# mapleCUx_large_085.net
KiCad netlist of a schematic drawn in EAGLE
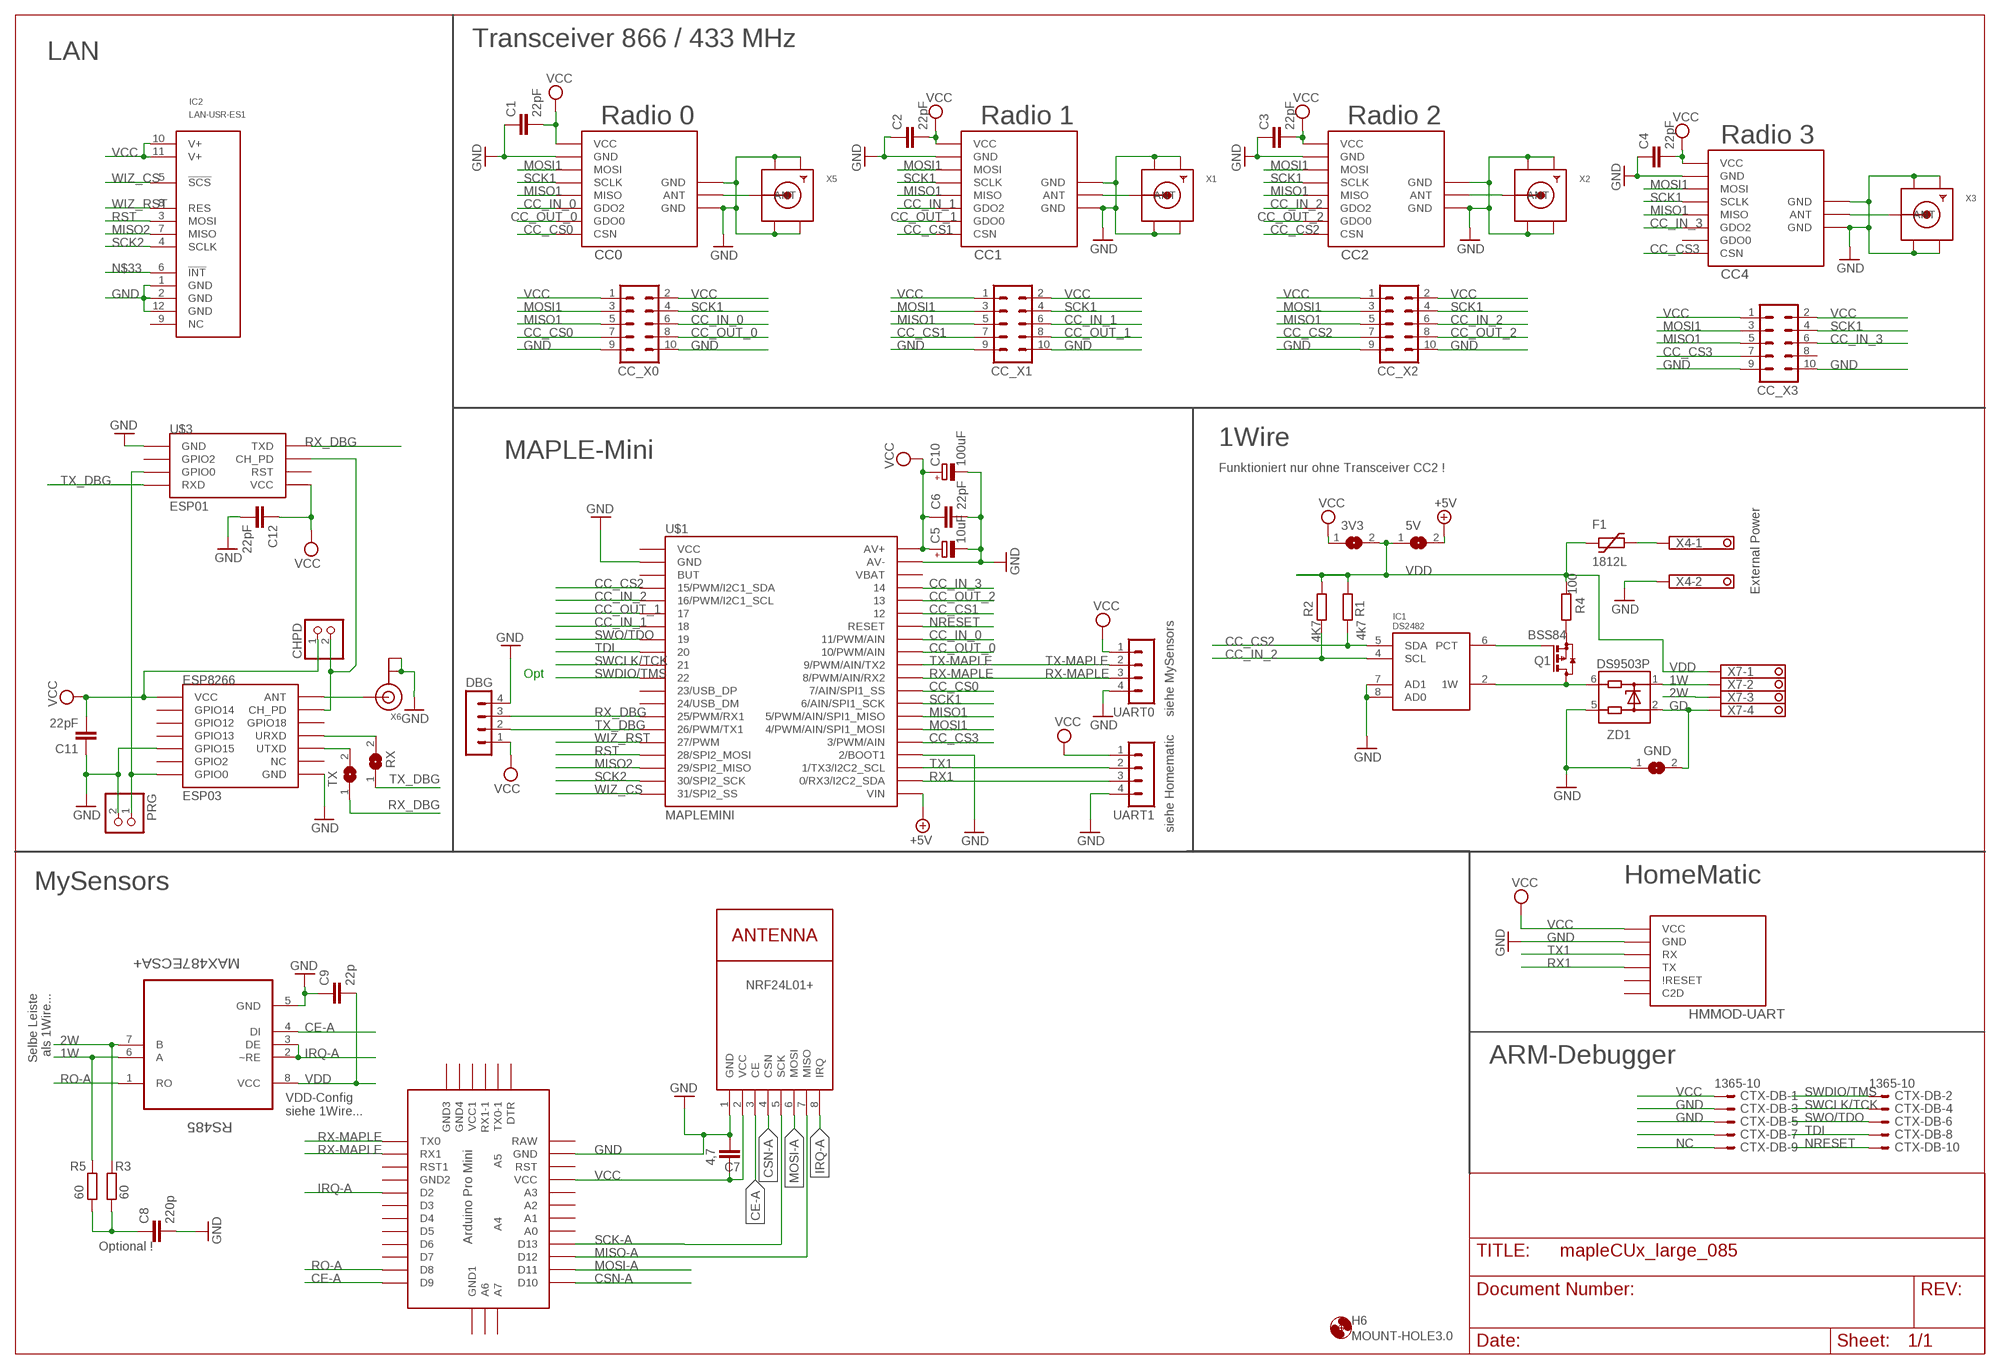
[diagram p0: schematic, sheet 1]

(export (version "E")
  (design (tool "Eeschema 10.0.6"))
  (components
    (comp (ref "3V3") (value "SJ") (footprint "eagle-import:SJ") (libsource (lib "eagle-import") (part "SJ")))
    (comp (ref "5V") (value "SJ") (footprint "eagle-import:SJ") (libsource (lib "eagle-import") (part "SJ")))
    (comp (ref "C1")
      (value "22pF")
      (footprint "eagle-import:C0805")
      (libsource (lib "eagle-import") (part "C-EUC0805"))
    )
    (comp (ref "C2")
      (value "22pF")
      (footprint "eagle-import:C0805")
      (libsource (lib "eagle-import") (part "C-EUC0805"))
    )
    (comp (ref "C3")
      (value "22pF")
      (footprint "eagle-import:C0805")
      (libsource (lib "eagle-import") (part "C-EUC0805"))
    )
    (comp (ref "C4")
      (value "22pF")
      (footprint "eagle-import:C0805")
      (libsource (lib "eagle-import") (part "C-EUC0805"))
    )
    (comp (ref "C5")
      (value "10uF")
      (footprint "eagle-import:R_2012-12W")
      (libsource (lib "eagle-import") (part "CPOL-EUR/2012-12W"))
    )
    (comp (ref "C6")
      (value "22pF")
      (footprint "eagle-import:C0805")
      (libsource (lib "eagle-import") (part "C-EUC0805"))
    )
    (comp (ref "C7")
      (value "4,7")
      (footprint "eagle-import:C1210")
      (libsource (lib "eagle-import") (part "C-EUC1210"))
    )
    (comp (ref "C8")
      (value "220p")
      (footprint "eagle-import:C0805")
      (libsource (lib "eagle-import") (part "C-EUC0805"))
    )
    (comp (ref "C9")
      (value "22p")
      (footprint "eagle-import:C0805")
      (libsource (lib "eagle-import") (part "C-EUC0805"))
    )
    (comp (ref "C10")
      (value "100uF")
      (footprint "eagle-import:E5-8,5")
      (libsource (lib "eagle-import") (part "CPOL-EUE5-8.5"))
    )
    (comp (ref "C11")
      (value "22pF")
      (footprint "eagle-import:C0805")
      (libsource (lib "eagle-import") (part "C-EUC0805"))
    )
    (comp (ref "C12")
      (value "22pF")
      (footprint "eagle-import:C0805")
      (libsource (lib "eagle-import") (part "C-EUC0805"))
    )
    (comp (ref "CC0")
      (value "CC1101")
      (footprint "eagle-import:CC1101_MODULE1_SMD")
      (libsource (lib "eagle-import") (part "CC1101_MODULE1SMD"))
    )
    (comp (ref "CC1")
      (value "CC1101_MODULE1SMD")
      (footprint "eagle-import:CC1101_MODULE1_SMD")
      (libsource (lib "eagle-import") (part "CC1101_MODULE1SMD"))
    )
    (comp (ref "CC2")
      (value "CC1101_MODULE1SMD")
      (footprint "eagle-import:CC1101_MODULE1_SMD")
      (libsource (lib "eagle-import") (part "CC1101_MODULE1SMD"))
    )
    (comp (ref "CC4")
      (value "CC1101_MODULE1SMD")
      (footprint "eagle-import:CC1101_MODULE1_SMD")
      (libsource (lib "eagle-import") (part "CC1101_MODULE1SMD"))
    )
    (comp (ref "CC_X0")
      (value "MA05-2")
      (footprint "eagle-import:MA05-2")
      (libsource (lib "eagle-import") (part "MA05-2"))
    )
    (comp (ref "CC_X1")
      (value "MA05-2")
      (footprint "eagle-import:MA05-2")
      (libsource (lib "eagle-import") (part "MA05-2"))
    )
    (comp (ref "CC_X2")
      (value "MA05-2")
      (footprint "eagle-import:MA05-2")
      (libsource (lib "eagle-import") (part "MA05-2"))
    )
    (comp (ref "CC_X3")
      (value "MA05-2")
      (footprint "eagle-import:MA05-2")
      (libsource (lib "eagle-import") (part "MA05-2"))
    )
    (comp (ref "CHPD")
      (value "PINHD-1X2")
      (footprint "eagle-import:1X02")
      (libsource (lib "eagle-import") (part "PINHD-1X2"))
    )
    (comp (ref "CTX-DB")
      (value "1365-10")
      (footprint "eagle-import:1365-10")
      (libsource (lib "eagle-import") (part "1365-10"))
    )
    (comp (ref "DBG")
      (value "MA04-1")
      (footprint "eagle-import:MA04-1")
      (libsource (lib "eagle-import") (part "MA04-1"))
    )
    (comp (ref "ESP8266")
      (value "ESP03")
      (footprint "eagle-import:ESP03")
      (libsource (lib "eagle-import") (part "ESP03"))
    )
    (comp (ref "F1")
      (value "1812L")
      (footprint "eagle-import:1812L")
      (libsource (lib "eagle-import") (part "1812L"))
    )
    (comp (ref "GND") (value "SJ") (footprint "eagle-import:SJ") (libsource (lib "eagle-import") (part "SJ")))
    (comp (ref "H6")
      (value "MOUNT-HOLE3.0")
      (footprint "eagle-import:3,0")
      (libsource (lib "eagle-import") (part "MOUNT-HOLE3.0"))
    )
    (comp (ref "HMMOD-UART")
      (value "HM-MOD-UARTDIL")
      (footprint "eagle-import:HM-MOD-UART-DIL")
      (libsource (lib "eagle-import") (part "HM-MOD-UARTDIL"))
    )
    (comp (ref "IC1")
      (value "DS2482")
      (footprint "eagle-import:SO08")
      (libsource (lib "eagle-import") (part "DS2482-100S"))
    )
    (comp (ref "IC2")
      (value "LAN-USR-ES1")
      (footprint "eagle-import:USR-ES1")
      (libsource (lib "eagle-import") (part "LAN-USR-ES1"))
    )
    (comp (ref "NRF24L01+")
      (value "NRF24L01+")
      (footprint "eagle-import:WIRELESS-NRF24L01")
      (libsource (lib "eagle-import") (part "WIRELESS-NRF24L01"))
    )
    (comp (ref "PRG")
      (value "PINHD-1X2")
      (footprint "eagle-import:1X02")
      (libsource (lib "eagle-import") (part "PINHD-1X2"))
    )
    (comp (ref "Q1")
      (value "BSS84")
      (footprint "eagle-import:SOT23")
      (libsource (lib "eagle-import") (part "BSS84"))
    )
    (comp (ref "R1")
      (value "4k7")
      (footprint "eagle-import:R0805")
      (libsource (lib "eagle-import") (part "R-EU_R0805"))
    )
    (comp (ref "R2")
      (value "4K7")
      (footprint "eagle-import:R0805")
      (libsource (lib "eagle-import") (part "R-EU_R0805"))
    )
    (comp (ref "R3")
      (value "60")
      (footprint "eagle-import:R0805")
      (libsource (lib "eagle-import") (part "R-EU_R0805"))
    )
    (comp (ref "R4")
      (value "100")
      (footprint "eagle-import:R0805")
      (libsource (lib "eagle-import") (part "R-EU_R0805"))
    )
    (comp (ref "R5")
      (value "60")
      (footprint "eagle-import:R0805")
      (libsource (lib "eagle-import") (part "R-EU_R0805"))
    )
    (comp (ref "RS485")
      (value "MAX487ECSA+")
      (footprint "eagle-import:SOIC127P600X175-8N")
      (libsource (lib "eagle-import") (part "MAX487ECSA+"))
    )
    (comp (ref "RX") (value "SJ") (footprint "eagle-import:SJ") (libsource (lib "eagle-import") (part "SJ")))
    (comp (ref "TX") (value "SJ") (footprint "eagle-import:SJ") (libsource (lib "eagle-import") (part "SJ")))
    (comp (ref "U$1")
      (value "MAPLEMINI")
      (footprint "eagle-import:20-DIP")
      (libsource (lib "eagle-import") (part "MAPLEMINI"))
    )
    (comp (ref "U$2")
      (value "ABK-PRO-MINI")
      (footprint "eagle-import:ABK-PRO-MINI")
      (libsource (lib "eagle-import") (part "ABK-PRO-MINI"))
    )
    (comp (ref "U$3")
      (value "ESP01")
      (footprint "eagle-import:ESP01")
      (libsource (lib "eagle-import") (part "ESP01"))
    )
    (comp (ref "UART0")
      (value "MA04-1")
      (footprint "eagle-import:MA04-1")
      (libsource (lib "eagle-import") (part "MA04-1"))
    )
    (comp (ref "UART1")
      (value "MA04-1")
      (footprint "eagle-import:MA04-1")
      (libsource (lib "eagle-import") (part "MA04-1"))
    )
    (comp (ref "X1")
      (value "SMACONNECTOR_EDGE_UFL")
      (footprint "eagle-import:SMA_EDGELAUNCH_UFL")
      (libsource (lib "eagle-import") (part "SMACONNECTOR_EDGE_UFL"))
    )
    (comp (ref "X2")
      (value "SMACONNECTOR_EDGE_UFL")
      (footprint "eagle-import:SMA_EDGELAUNCH_UFL")
      (libsource (lib "eagle-import") (part "SMACONNECTOR_EDGE_UFL"))
    )
    (comp (ref "X3")
      (value "SMACONNECTOR_EDGE_UFL")
      (footprint "eagle-import:SMA_EDGELAUNCH_UFL")
      (libsource (lib "eagle-import") (part "SMACONNECTOR_EDGE_UFL"))
    )
    (comp (ref "X4")
      (value "1751248")
      (footprint "eagle-import:1751248")
      (libsource (lib "eagle-import") (part "1751248"))
    )
    (comp (ref "X5")
      (value "SMACONNECTOR_EDGE_UFL")
      (footprint "eagle-import:SMA_EDGELAUNCH_UFL")
      (libsource (lib "eagle-import") (part "SMACONNECTOR_EDGE_UFL"))
    )
    (comp (ref "X6")
      (value "ANTENNA_U.FL")
      (footprint "eagle-import:U.FL")
      (libsource (lib "eagle-import") (part "ANTENNA_U.FL"))
    )
    (comp (ref "X7")
      (value "1751264")
      (footprint "eagle-import:1751264")
      (libsource (lib "eagle-import") (part "1751264"))
    )
    (comp (ref "ZD1")
      (value "DS9503P")
      (footprint "eagle-import:TSOC6")
      (libsource (lib "eagle-import") (part "DS9503P"))
    )
  )
  (nets
    (net (code "1") (name "+5V") (class "Default")
      (node (ref "5V") (pin "2") (pinfunction "2_2") (pintype "passive"))
      (node (ref "U$1") (pin "21") (pinfunction "VIN_21") (pintype "bidirectional"))
    )
    (net (code "2") (name "/1W") (class "Default")
      (node (ref "R5") (pin "2") (pinfunction "2_2") (pintype "passive"))
      (node (ref "RS485") (pin "6") (pinfunction "A_6") (pintype "bidirectional"))
      (node (ref "X7") (pin "2") (pinfunction "K_2") (pintype "passive"))
      (node (ref "ZD1") (pin "1") (pinfunction "P$1_1") (pintype "passive"))
    )
    (net (code "3") (name "/2W") (class "Default")
      (node (ref "R3") (pin "2") (pinfunction "2_2") (pintype "passive"))
      (node (ref "RS485") (pin "7") (pinfunction "B_7") (pintype "bidirectional"))
      (node (ref "X7") (pin "3") (pinfunction "K_3") (pintype "passive"))
    )
    (net (code "4") (name "/CC_CS0") (class "Default")
      (node (ref "CC0") (pin "CSN") (pinfunction "CSN_CSN") (pintype "bidirectional"))
      (node (ref "CC_X0") (pin "7") (pinfunction "7_7") (pintype "passive"))
      (node (ref "U$1") (pin "29") (pinfunction "7/AIN/SPI1_SS_29") (pintype "bidirectional"))
    )
    (net (code "5") (name "/CC_CS1") (class "Default")
      (node (ref "CC1") (pin "CSN") (pinfunction "CSN_CSN") (pintype "bidirectional"))
      (node (ref "CC_X1") (pin "7") (pinfunction "7_7") (pintype "passive"))
      (node (ref "U$1") (pin "35") (pinfunction "12_35") (pintype "bidirectional"))
    )
    (net (code "6") (name "/CC_CS2") (class "Default")
      (node (ref "CC2") (pin "CSN") (pinfunction "CSN_CSN") (pintype "bidirectional"))
      (node (ref "CC_X2") (pin "7") (pinfunction "7_7") (pintype "passive"))
      (node (ref "IC1") (pin "5") (pinfunction "SDA_5") (pintype "bidirectional"))
      (node (ref "R1") (pin "2") (pinfunction "2_2") (pintype "passive"))
      (node (ref "U$1") (pin "4") (pinfunction "15/PWM/I2C1_SDA_4") (pintype "bidirectional"))
    )
    (net (code "7") (name "/CC_CS3") (class "Default")
      (node (ref "CC4") (pin "CSN") (pinfunction "CSN_CSN") (pintype "bidirectional"))
      (node (ref "CC_X3") (pin "7") (pinfunction "7_7") (pintype "passive"))
      (node (ref "U$1") (pin "25") (pinfunction "3/PWM/AIN_25") (pintype "bidirectional"))
    )
    (net (code "8") (name "/CC_IN_0") (class "Default")
      (node (ref "CC0") (pin "GDO2") (pinfunction "GDO2_GDO2") (pintype "bidirectional"))
      (node (ref "CC_X0") (pin "6") (pinfunction "6_6") (pintype "passive"))
      (node (ref "U$1") (pin "33") (pinfunction "11/PWM/AIN_33") (pintype "bidirectional"))
    )
    (net (code "9") (name "/CC_IN_1") (class "Default")
      (node (ref "CC1") (pin "GDO2") (pinfunction "GDO2_GDO2") (pintype "bidirectional"))
      (node (ref "CC_X1") (pin "6") (pinfunction "6_6") (pintype "passive"))
      (node (ref "U$1") (pin "7") (pinfunction "18_7") (pintype "bidirectional"))
    )
    (net (code "10") (name "/CC_IN_2") (class "Default")
      (node (ref "CC2") (pin "GDO2") (pinfunction "GDO2_GDO2") (pintype "bidirectional"))
      (node (ref "CC_X2") (pin "6") (pinfunction "6_6") (pintype "passive"))
      (node (ref "IC1") (pin "4") (pinfunction "SCL_4") (pintype "input"))
      (node (ref "R2") (pin "2") (pinfunction "2_2") (pintype "passive"))
      (node (ref "U$1") (pin "5") (pinfunction "16/PWM/I2C1_SCL_5") (pintype "bidirectional"))
    )
    (net (code "11") (name "/CC_IN_3") (class "Default")
      (node (ref "CC4") (pin "GDO2") (pinfunction "GDO2_GDO2") (pintype "bidirectional"))
      (node (ref "CC_X3") (pin "6") (pinfunction "6_6") (pintype "passive"))
      (node (ref "U$1") (pin "37") (pinfunction "14_37") (pintype "bidirectional"))
    )
    (net (code "12") (name "/CC_OUT_0") (class "Default")
      (node (ref "CC0") (pin "GDO0") (pinfunction "GDO0_GDO0") (pintype "bidirectional"))
      (node (ref "CC_X0") (pin "8") (pinfunction "8_8") (pintype "passive"))
      (node (ref "U$1") (pin "32") (pinfunction "10/PWM/AIN_32") (pintype "bidirectional"))
    )
    (net (code "13") (name "/CC_OUT_1") (class "Default")
      (node (ref "CC1") (pin "GDO0") (pinfunction "GDO0_GDO0") (pintype "bidirectional"))
      (node (ref "CC_X1") (pin "8") (pinfunction "8_8") (pintype "passive"))
      (node (ref "U$1") (pin "6") (pinfunction "17_6") (pintype "bidirectional"))
    )
    (net (code "14") (name "/CC_OUT_2") (class "Default")
      (node (ref "CC2") (pin "GDO0") (pinfunction "GDO0_GDO0") (pintype "bidirectional"))
      (node (ref "CC_X2") (pin "8") (pinfunction "8_8") (pintype "passive"))
      (node (ref "U$1") (pin "36") (pinfunction "13_36") (pintype "bidirectional"))
    )
    (net (code "15") (name "/GD") (class "Default")
      (node (ref "GND") (pin "2") (pinfunction "2_2") (pintype "passive"))
      (node (ref "X7") (pin "4") (pinfunction "K_4") (pintype "passive"))
      (node (ref "ZD1") (pin "2") (pinfunction "P$2_2") (pintype "passive"))
    )
    (net (code "16") (name "/MISO-A") (class "Default")
      (node (ref "NRF24L01+") (pin "7") (pinfunction "MISO_7") (pintype "bidirectional"))
      (node (ref "U$2") (pin "D12") (pinfunction "D12_D12") (pintype "bidirectional"))
    )
    (net (code "17") (name "/MISO1") (class "Default")
      (node (ref "CC0") (pin "MISO") (pinfunction "MISO_MISO") (pintype "bidirectional"))
      (node (ref "CC1") (pin "MISO") (pinfunction "MISO_MISO") (pintype "bidirectional"))
      (node (ref "CC2") (pin "MISO") (pinfunction "MISO_MISO") (pintype "bidirectional"))
      (node (ref "CC4") (pin "MISO") (pinfunction "MISO_MISO") (pintype "bidirectional"))
      (node (ref "CC_X0") (pin "5") (pinfunction "5_5") (pintype "passive"))
      (node (ref "CC_X1") (pin "5") (pinfunction "5_5") (pintype "passive"))
      (node (ref "CC_X2") (pin "5") (pinfunction "5_5") (pintype "passive"))
      (node (ref "CC_X3") (pin "5") (pinfunction "5_5") (pintype "passive"))
      (node (ref "U$1") (pin "27") (pinfunction "5/PWM/AIN/SPI1_MISO_27") (pintype "bidirectional"))
    )
    (net (code "18") (name "/MISO2") (class "Default")
      (node (ref "IC2") (pin "7") (pinfunction "MISO_7") (pintype "bidirectional"))
      (node (ref "U$1") (pin "18") (pinfunction "29/SPI2_MISO_18") (pintype "bidirectional"))
    )
    (net (code "19") (name "/MOSI1") (class "Default")
      (node (ref "CC0") (pin "MOSI") (pinfunction "MOSI_MOSI") (pintype "bidirectional"))
      (node (ref "CC1") (pin "MOSI") (pinfunction "MOSI_MOSI") (pintype "bidirectional"))
      (node (ref "CC2") (pin "MOSI") (pinfunction "MOSI_MOSI") (pintype "bidirectional"))
      (node (ref "CC4") (pin "MOSI") (pinfunction "MOSI_MOSI") (pintype "bidirectional"))
      (node (ref "CC_X0") (pin "3") (pinfunction "3_3") (pintype "passive"))
      (node (ref "CC_X1") (pin "3") (pinfunction "3_3") (pintype "passive"))
      (node (ref "CC_X2") (pin "3") (pinfunction "3_3") (pintype "passive"))
      (node (ref "CC_X3") (pin "3") (pinfunction "3_3") (pintype "passive"))
      (node (ref "U$1") (pin "26") (pinfunction "4/PWM/AIN/SPI1_MOSI_26") (pintype "bidirectional"))
    )
    (net (code "20") (name "/N$33") (class "Default")
      (node (ref "IC2") (pin "6") (pinfunction "~{INT}_6") (pintype "output"))
    )
    (net (code "21") (name "/NC") (class "Default")
      (node (ref "CTX-DB") (pin "9") (pinfunction "S_9") (pintype "passive"))
    )
    (net (code "22") (name "/NRESET") (class "Default")
      (node (ref "CTX-DB") (pin "10") (pinfunction "S_10") (pintype "passive"))
      (node (ref "U$1") (pin "34") (pinfunction "RESET_34") (pintype "bidirectional"))
    )
    (net (code "23") (name "/RO-A") (class "Default")
      (node (ref "RS485") (pin "1") (pinfunction "RO_1") (pintype "output"))
      (node (ref "U$2") (pin "D8") (pinfunction "D8_D8") (pintype "bidirectional"))
    )
    (net (code "24") (name "/RST") (class "Default")
      (node (ref "IC2") (pin "3") (pinfunction "MOSI_3") (pintype "bidirectional"))
      (node (ref "U$1") (pin "17") (pinfunction "28/SPI2_MOSI_17") (pintype "bidirectional"))
    )
    (net (code "25") (name "/RX-MAPLE") (class "Default")
      (node (ref "U$1") (pin "30") (pinfunction "8/PWM/AIN/RX2_30") (pintype "bidirectional"))
      (node (ref "U$2") (pin "RX1") (pinfunction "RX1_RX1") (pintype "bidirectional"))
      (node (ref "U$2") (pin "TX0") (pinfunction "TX0_TX0") (pintype "bidirectional"))
      (node (ref "UART0") (pin "3") (pinfunction "3_3") (pintype "passive"))
    )
    (net (code "26") (name "/RX1") (class "Default")
      (node (ref "HMMOD-UART") (pin "5") (pinfunction "TX_5") (pintype "bidirectional"))
      (node (ref "U$1") (pin "22") (pinfunction "0/RX3/I2C2_SDA_22") (pintype "bidirectional"))
      (node (ref "UART1") (pin "3") (pinfunction "3_3") (pintype "passive"))
    )
    (net (code "27") (name "/RX_DBG") (class "Default")
      (node (ref "DBG") (pin "3") (pinfunction "3_3") (pintype "passive"))
      (node (ref "TX") (pin "1") (pinfunction "1_1") (pintype "passive"))
      (node (ref "U$1") (pin "14") (pinfunction "25/PWM/RX1_14") (pintype "bidirectional"))
      (node (ref "U$3") (pin "TX") (pinfunction "TXD_TX") (pintype "bidirectional"))
    )
    (net (code "28") (name "/SCK-A") (class "Default")
      (node (ref "NRF24L01+") (pin "5") (pinfunction "SCK_5") (pintype "bidirectional"))
      (node (ref "U$2") (pin "D13") (pinfunction "D13_D13") (pintype "bidirectional"))
    )
    (net (code "29") (name "/SCK1") (class "Default")
      (node (ref "CC0") (pin "SCLK") (pinfunction "SCLK_SCLK") (pintype "bidirectional"))
      (node (ref "CC1") (pin "SCLK") (pinfunction "SCLK_SCLK") (pintype "bidirectional"))
      (node (ref "CC2") (pin "SCLK") (pinfunction "SCLK_SCLK") (pintype "bidirectional"))
      (node (ref "CC4") (pin "SCLK") (pinfunction "SCLK_SCLK") (pintype "bidirectional"))
      (node (ref "CC_X0") (pin "4") (pinfunction "4_4") (pintype "passive"))
      (node (ref "CC_X1") (pin "4") (pinfunction "4_4") (pintype "passive"))
      (node (ref "CC_X2") (pin "4") (pinfunction "4_4") (pintype "passive"))
      (node (ref "CC_X3") (pin "4") (pinfunction "4_4") (pintype "passive"))
      (node (ref "U$1") (pin "28") (pinfunction "6/AIN/SPI1_SCK_28") (pintype "bidirectional"))
    )
    (net (code "30") (name "/SCK2") (class "Default")
      (node (ref "IC2") (pin "4") (pinfunction "SCLK_4") (pintype "input"))
      (node (ref "U$1") (pin "19") (pinfunction "30/SPI2_SCK_19") (pintype "bidirectional"))
    )
    (net (code "31") (name "/SWCLK{slash}TCK") (class "Default")
      (node (ref "CTX-DB") (pin "4") (pinfunction "S_4") (pintype "passive"))
      (node (ref "U$1") (pin "10") (pinfunction "21_10") (pintype "bidirectional"))
    )
    (net (code "32") (name "/SWDIO{slash}TMS") (class "Default")
      (node (ref "CTX-DB") (pin "2") (pinfunction "S_2") (pintype "passive"))
      (node (ref "U$1") (pin "11") (pinfunction "22_11") (pintype "bidirectional"))
    )
    (net (code "33") (name "/SWO{slash}TDO") (class "Default")
      (node (ref "CTX-DB") (pin "6") (pinfunction "S_6") (pintype "passive"))
      (node (ref "U$1") (pin "8") (pinfunction "19_8") (pintype "bidirectional"))
    )
    (net (code "34") (name "/TDI") (class "Default")
      (node (ref "CTX-DB") (pin "8") (pinfunction "S_8") (pintype "passive"))
      (node (ref "U$1") (pin "9") (pinfunction "20_9") (pintype "bidirectional"))
    )
    (net (code "35") (name "/TX-MAPLE") (class "Default")
      (node (ref "U$1") (pin "31") (pinfunction "9/PWM/AIN/TX2_31") (pintype "bidirectional"))
      (node (ref "UART0") (pin "2") (pinfunction "2_2") (pintype "passive"))
    )
    (net (code "36") (name "/TX1") (class "Default")
      (node (ref "HMMOD-UART") (pin "6") (pinfunction "RX_6") (pintype "bidirectional"))
      (node (ref "U$1") (pin "23") (pinfunction "1/TX3/I2C2_SCL_23") (pintype "bidirectional"))
      (node (ref "UART1") (pin "2") (pinfunction "2_2") (pintype "passive"))
    )
    (net (code "37") (name "/TX_DBG") (class "Default")
      (node (ref "DBG") (pin "2") (pinfunction "2_2") (pintype "passive"))
      (node (ref "RX") (pin "1") (pinfunction "1_1") (pintype "passive"))
      (node (ref "U$1") (pin "15") (pinfunction "26/PWM/TX1_15") (pintype "bidirectional"))
      (node (ref "U$3") (pin "RX") (pinfunction "RXD_RX") (pintype "bidirectional"))
    )
    (net (code "38") (name "/VDD") (class "Default")
      (node (ref "3V3") (pin "2") (pinfunction "2_2") (pintype "passive"))
      (node (ref "5V") (pin "1") (pinfunction "1_1") (pintype "passive"))
      (node (ref "C9") (pin "2") (pinfunction "2_2") (pintype "passive"))
      (node (ref "F1") (pin "P$1") (pinfunction "1_P$1") (pintype "passive"))
      (node (ref "R1") (pin "1") (pinfunction "1_1") (pintype "passive"))
      (node (ref "R2") (pin "1") (pinfunction "1_1") (pintype "passive"))
      (node (ref "R4") (pin "2") (pinfunction "2_2") (pintype "passive"))
      (node (ref "RS485") (pin "8") (pinfunction "VCC_8") (pintype "power_in"))
      (node (ref "X7") (pin "1") (pinfunction "K_1") (pintype "passive"))
    )
    (net (code "39") (name "/WIZ_CS") (class "Default")
      (node (ref "IC2") (pin "5") (pinfunction "~{SCS}_5") (pintype "input"))
      (node (ref "U$1") (pin "20") (pinfunction "31/SPI2_SS_20") (pintype "bidirectional"))
    )
    (net (code "40") (name "/WIZ_RST") (class "Default")
      (node (ref "IC2") (pin "8") (pinfunction "RES_8") (pintype "input"))
      (node (ref "U$1") (pin "16") (pinfunction "27/PWM_16") (pintype "bidirectional"))
    )
    (net (code "41") (name "CE-A") (class "Default")
      (node (ref "NRF24L01+") (pin "3") (pinfunction "CE_3") (pintype "bidirectional"))
      (node (ref "RS485") (pin "4") (pinfunction "DI_4") (pintype "input"))
      (node (ref "U$2") (pin "D9") (pinfunction "D9_D9") (pintype "bidirectional"))
    )
    (net (code "42") (name "CSN-A") (class "Default")
      (node (ref "NRF24L01+") (pin "4") (pinfunction "CSN_4") (pintype "bidirectional"))
      (node (ref "U$2") (pin "D10") (pinfunction "D10_D10") (pintype "bidirectional"))
    )
    (net (code "43") (name "GND") (class "Default")
      (node (ref "C1") (pin "1") (pinfunction "1_1") (pintype "passive"))
      (node (ref "C10") (pin "-") (pinfunction "-_-") (pintype "passive"))
      (node (ref "C11") (pin "1") (pinfunction "1_1") (pintype "passive"))
      (node (ref "C12") (pin "2") (pinfunction "2_2") (pintype "passive"))
      (node (ref "C2") (pin "1") (pinfunction "1_1") (pintype "passive"))
      (node (ref "C3") (pin "1") (pinfunction "1_1") (pintype "passive"))
      (node (ref "C4") (pin "1") (pinfunction "1_1") (pintype "passive"))
      (node (ref "C5") (pin "-") (pinfunction "-_-") (pintype "passive"))
      (node (ref "C6") (pin "2") (pinfunction "2_2") (pintype "passive"))
      (node (ref "C7") (pin "1") (pinfunction "1_1") (pintype "passive"))
      (node (ref "C8") (pin "2") (pinfunction "2_2") (pintype "passive"))
      (node (ref "C9") (pin "1") (pinfunction "1_1") (pintype "passive"))
      (node (ref "CC0") (pin "GND@0") (pinfunction "GND_GND@0") (pintype "power_in"))
      (node (ref "CC0") (pin "GND@1") (pinfunction "GND_GND@1") (pintype "power_in"))
      (node (ref "CC0") (pin "GND@2") (pinfunction "GND_GND@2") (pintype "power_in"))
      (node (ref "CC1") (pin "GND@0") (pinfunction "GND_GND@0") (pintype "power_in"))
      (node (ref "CC1") (pin "GND@1") (pinfunction "GND_GND@1") (pintype "power_in"))
      (node (ref "CC1") (pin "GND@2") (pinfunction "GND_GND@2") (pintype "power_in"))
      (node (ref "CC2") (pin "GND@0") (pinfunction "GND_GND@0") (pintype "power_in"))
      (node (ref "CC2") (pin "GND@1") (pinfunction "GND_GND@1") (pintype "power_in"))
      (node (ref "CC2") (pin "GND@2") (pinfunction "GND_GND@2") (pintype "power_in"))
      (node (ref "CC4") (pin "GND@0") (pinfunction "GND_GND@0") (pintype "power_in"))
      (node (ref "CC4") (pin "GND@1") (pinfunction "GND_GND@1") (pintype "power_in"))
      (node (ref "CC4") (pin "GND@2") (pinfunction "GND_GND@2") (pintype "power_in"))
      (node (ref "CC_X0") (pin "10") (pinfunction "10_10") (pintype "passive"))
      (node (ref "CC_X0") (pin "9") (pinfunction "9_9") (pintype "passive"))
      (node (ref "CC_X1") (pin "10") (pinfunction "10_10") (pintype "passive"))
      (node (ref "CC_X1") (pin "9") (pinfunction "9_9") (pintype "passive"))
      (node (ref "CC_X2") (pin "10") (pinfunction "10_10") (pintype "passive"))
      (node (ref "CC_X2") (pin "9") (pinfunction "9_9") (pintype "passive"))
      (node (ref "CC_X3") (pin "10") (pinfunction "10_10") (pintype "passive"))
      (node (ref "CC_X3") (pin "9") (pinfunction "9_9") (pintype "passive"))
      (node (ref "CTX-DB") (pin "3") (pinfunction "S_3") (pintype "passive"))
      (node (ref "CTX-DB") (pin "5") (pinfunction "S_5") (pintype "passive"))
      (node (ref "DBG") (pin "4") (pinfunction "4_4") (pintype "passive"))
      (node (ref "ESP8266") (pin "GND") (pinfunction "GND_GND") (pintype "bidirectional"))
      (node (ref "ESP8266") (pin "GPIO15") (pinfunction "GPIO15_GPIO15") (pintype "bidirectional"))
      (node (ref "GND") (pin "1") (pinfunction "1_1") (pintype "passive"))
      (node (ref "HMMOD-UART") (pin "2") (pinfunction "GND_2") (pintype "power_in"))
      (node (ref "IC1") (pin "7") (pinfunction "AD1_7") (pintype "input"))
      (node (ref "IC1") (pin "8") (pinfunction "AD0_8") (pintype "input"))
      (node (ref "IC2") (pin "1") (pinfunction "GND_1") (pintype "power_in"))
      (node (ref "IC2") (pin "12") (pinfunction "GND_12") (pintype "power_in"))
      (node (ref "IC2") (pin "2") (pinfunction "GND_2") (pintype "power_in"))
      (node (ref "NRF24L01+") (pin "1") (pinfunction "GND_1") (pintype "power_in"))
      (node (ref "PRG") (pin "2") (pinfunction "2_2") (pintype "passive"))
      (node (ref "RS485") (pin "5") (pinfunction "GND_5") (pintype "passive"))
      (node (ref "U$1") (pin "2") (pinfunction "GND_2") (pintype "bidirectional"))
      (node (ref "U$1") (pin "24") (pinfunction "2/BOOT1_24") (pintype "bidirectional"))
      (node (ref "U$1") (pin "39") (pinfunction "AV-_39") (pintype "bidirectional"))
      (node (ref "U$2") (pin "GND") (pinfunction "GND_GND") (pintype "bidirectional"))
      (node (ref "U$3") (pin "GND") (pinfunction "GND_GND") (pintype "bidirectional"))
      (node (ref "UART0") (pin "4") (pinfunction "4_4") (pintype "passive"))
      (node (ref "UART1") (pin "4") (pinfunction "4_4") (pintype "passive"))
      (node (ref "X1") (pin "GND@1") (pinfunction "GND1_GND@1") (pintype "power_in"))
      (node (ref "X1") (pin "GND@2") (pinfunction "GND2_GND@2") (pintype "power_in"))
      (node (ref "X1") (pin "GND@3") (pinfunction "GND3_GND@3") (pintype "power_in"))
      (node (ref "X1") (pin "GND@4") (pinfunction "GND4_GND@4") (pintype "power_in"))
      (node (ref "X2") (pin "GND@1") (pinfunction "GND1_GND@1") (pintype "power_in"))
      (node (ref "X2") (pin "GND@2") (pinfunction "GND2_GND@2") (pintype "power_in"))
      (node (ref "X2") (pin "GND@3") (pinfunction "GND3_GND@3") (pintype "power_in"))
      (node (ref "X2") (pin "GND@4") (pinfunction "GND4_GND@4") (pintype "power_in"))
      (node (ref "X3") (pin "GND@1") (pinfunction "GND1_GND@1") (pintype "power_in"))
      (node (ref "X3") (pin "GND@2") (pinfunction "GND2_GND@2") (pintype "power_in"))
      (node (ref "X3") (pin "GND@3") (pinfunction "GND3_GND@3") (pintype "power_in"))
      (node (ref "X3") (pin "GND@4") (pinfunction "GND4_GND@4") (pintype "power_in"))
      (node (ref "X4") (pin "2") (pinfunction "K_2") (pintype "passive"))
      (node (ref "X5") (pin "GND@1") (pinfunction "GND1_GND@1") (pintype "power_in"))
      (node (ref "X5") (pin "GND@2") (pinfunction "GND2_GND@2") (pintype "power_in"))
      (node (ref "X5") (pin "GND@3") (pinfunction "GND3_GND@3") (pintype "power_in"))
      (node (ref "X5") (pin "GND@4") (pinfunction "GND4_GND@4") (pintype "power_in"))
      (node (ref "X6") (pin "1") (pinfunction "GND_1") (pintype "passive"))
      (node (ref "X6") (pin "2") (pinfunction "GND_2") (pintype "passive"))
      (node (ref "ZD1") (pin "5") (pinfunction "P$3_5") (pintype "passive"))
    )
    (net (code "44") (name "IRQ-A") (class "Default")
      (node (ref "NRF24L01+") (pin "8") (pinfunction "IRQ_8") (pintype "bidirectional"))
      (node (ref "RS485") (pin "2") (pinfunction "~{RE}_2") (pintype "input"))
      (node (ref "RS485") (pin "3") (pinfunction "DE_3") (pintype "input"))
      (node (ref "U$2") (pin "D2") (pinfunction "D2_D2") (pintype "bidirectional"))
    )
    (net (code "45") (name "MOSI-A") (class "Default")
      (node (ref "NRF24L01+") (pin "6") (pinfunction "MOSI_6") (pintype "bidirectional"))
      (node (ref "U$2") (pin "D11") (pinfunction "D11_D11") (pintype "bidirectional"))
    )
    (net (code "46") (name "Net-(C8-Pad1)") (class "Default")
      (node (ref "C8") (pin "1") (pinfunction "1_1") (pintype "passive"))
      (node (ref "R3") (pin "1") (pinfunction "1_1") (pintype "passive"))
      (node (ref "R5") (pin "1") (pinfunction "1_1") (pintype "passive"))
    )
    (net (code "47") (name "Net-(CHPD-Pad2)") (class "Default")
      (node (ref "CHPD") (pin "2") (pinfunction "2_2") (pintype "passive"))
      (node (ref "ESP8266") (pin "CH_PD") (pinfunction "CH_PD_CH_PD") (pintype "bidirectional"))
      (node (ref "U$3") (pin "CH_PD") (pinfunction "CH_PD_CH_PD") (pintype "bidirectional"))
    )
    (net (code "48") (name "Net-(ESP8266-PadGPIO0)") (class "Default")
      (node (ref "ESP8266") (pin "GPIO0") (pinfunction "GPIO0_GPIO0") (pintype "bidirectional"))
      (node (ref "PRG") (pin "1") (pinfunction "1_1") (pintype "passive"))
      (node (ref "U$3") (pin "GPIO0") (pinfunction "GPIO0_GPIO0") (pintype "bidirectional"))
    )
    (net (code "49") (name "Net-(ESP8266-PadURXD)") (class "Default")
      (node (ref "ESP8266") (pin "URXD") (pinfunction "URXD_URXD") (pintype "bidirectional"))
      (node (ref "RX") (pin "2") (pinfunction "2_2") (pintype "passive"))
    )
    (net (code "50") (name "Net-(ESP8266-PadUTXD)") (class "Default")
      (node (ref "ESP8266") (pin "UTXD") (pinfunction "UTXD_UTXD") (pintype "bidirectional"))
      (node (ref "TX") (pin "2") (pinfunction "2_2") (pintype "passive"))
    )
    (net (code "51") (name "Net-(F1-2)") (class "Default")
      (node (ref "F1") (pin "P$2") (pinfunction "2_P$2") (pintype "passive"))
      (node (ref "X4") (pin "1") (pinfunction "K_1") (pintype "passive"))
    )
    (net (code "52") (name "Net-(IC1A-1W)") (class "Default")
      (node (ref "IC1") (pin "2") (pinfunction "1W_2") (pintype "open_collector"))
      (node (ref "Q1") (pin "3") (pinfunction "D_3") (pintype "passive"))
      (node (ref "ZD1") (pin "6") (pinfunction "P$4_6") (pintype "passive"))
    )
    (net (code "53") (name "Net-(IC1A-PCT)") (class "Default")
      (node (ref "IC1") (pin "6") (pinfunction "PCT_6") (pintype "output"))
      (node (ref "Q1") (pin "1") (pinfunction "G_1") (pintype "passive"))
    )
    (net (code "54") (name "Net-(Q1-S)") (class "Default")
      (node (ref "Q1") (pin "2") (pinfunction "S_2") (pintype "passive"))
      (node (ref "R4") (pin "1") (pinfunction "1_1") (pintype "passive"))
    )
    (net (code "55") (name "Net-(X1-ANT)") (class "Default")
      (node (ref "CC1") (pin "ANT") (pinfunction "ANT_ANT") (pintype "output"))
      (node (ref "X1") (pin "P") (pinfunction "ANT_P") (pintype "bidirectional"))
    )
    (net (code "56") (name "Net-(X2-ANT)") (class "Default")
      (node (ref "CC2") (pin "ANT") (pinfunction "ANT_ANT") (pintype "output"))
      (node (ref "X2") (pin "P") (pinfunction "ANT_P") (pintype "bidirectional"))
    )
    (net (code "57") (name "Net-(X3-ANT)") (class "Default")
      (node (ref "CC4") (pin "ANT") (pinfunction "ANT_ANT") (pintype "output"))
      (node (ref "X3") (pin "P") (pinfunction "ANT_P") (pintype "bidirectional"))
    )
    (net (code "58") (name "Net-(X5-ANT)") (class "Default")
      (node (ref "CC0") (pin "ANT") (pinfunction "ANT_ANT") (pintype "output"))
      (node (ref "X5") (pin "P") (pinfunction "ANT_P") (pintype "bidirectional"))
    )
    (net (code "59") (name "Net-(X6-SIGNAL)") (class "Default")
      (node (ref "ESP8266") (pin "ANT") (pinfunction "ANT_ANT") (pintype "bidirectional"))
      (node (ref "X6") (pin "3") (pinfunction "SIGNAL_3") (pintype "passive"))
    )
    (net (code "60") (name "VCC") (class "Default")
      (node (ref "3V3") (pin "1") (pinfunction "1_1") (pintype "passive"))
      (node (ref "C1") (pin "2") (pinfunction "2_2") (pintype "passive"))
      (node (ref "C10") (pin "+") (pinfunction "+_+") (pintype "passive"))
      (node (ref "C11") (pin "2") (pinfunction "2_2") (pintype "passive"))
      (node (ref "C12") (pin "1") (pinfunction "1_1") (pintype "passive"))
      (node (ref "C2") (pin "2") (pinfunction "2_2") (pintype "passive"))
      (node (ref "C3") (pin "2") (pinfunction "2_2") (pintype "passive"))
      (node (ref "C4") (pin "2") (pinfunction "2_2") (pintype "passive"))
      (node (ref "C5") (pin "+") (pinfunction "+_+") (pintype "passive"))
      (node (ref "C6") (pin "1") (pinfunction "1_1") (pintype "passive"))
      (node (ref "C7") (pin "2") (pinfunction "2_2") (pintype "passive"))
      (node (ref "CC0") (pin "VCC") (pinfunction "VCC_VCC") (pintype "power_in"))
      (node (ref "CC1") (pin "VCC") (pinfunction "VCC_VCC") (pintype "power_in"))
      (node (ref "CC2") (pin "VCC") (pinfunction "VCC_VCC") (pintype "power_in"))
      (node (ref "CC4") (pin "VCC") (pinfunction "VCC_VCC") (pintype "power_in"))
      (node (ref "CC_X0") (pin "1") (pinfunction "1_1") (pintype "passive"))
      (node (ref "CC_X0") (pin "2") (pinfunction "2_2") (pintype "passive"))
      (node (ref "CC_X1") (pin "1") (pinfunction "1_1") (pintype "passive"))
      (node (ref "CC_X1") (pin "2") (pinfunction "2_2") (pintype "passive"))
      (node (ref "CC_X2") (pin "1") (pinfunction "1_1") (pintype "passive"))
      (node (ref "CC_X2") (pin "2") (pinfunction "2_2") (pintype "passive"))
      (node (ref "CC_X3") (pin "1") (pinfunction "1_1") (pintype "passive"))
      (node (ref "CC_X3") (pin "2") (pinfunction "2_2") (pintype "passive"))
      (node (ref "CHPD") (pin "1") (pinfunction "1_1") (pintype "passive"))
      (node (ref "CTX-DB") (pin "1") (pinfunction "S_1") (pintype "passive"))
      (node (ref "DBG") (pin "1") (pinfunction "1_1") (pintype "passive"))
      (node (ref "ESP8266") (pin "VCC") (pinfunction "VCC_VCC") (pintype "bidirectional"))
      (node (ref "HMMOD-UART") (pin "1") (pinfunction "VCC_1") (pintype "power_in"))
      (node (ref "IC2") (pin "10") (pinfunction "V+_10") (pintype "power_in"))
      (node (ref "IC2") (pin "11") (pinfunction "V+_11") (pintype "power_in"))
      (node (ref "NRF24L01+") (pin "2") (pinfunction "VCC_2") (pintype "power_in"))
      (node (ref "U$1") (pin "40") (pinfunction "AV+_40") (pintype "bidirectional"))
      (node (ref "U$2") (pin "VCC") (pinfunction "VCC_VCC") (pintype "bidirectional"))
      (node (ref "U$3") (pin "VCC") (pinfunction "VCC_VCC") (pintype "bidirectional"))
      (node (ref "UART0") (pin "1") (pinfunction "1_1") (pintype "passive"))
      (node (ref "UART1") (pin "1") (pinfunction "1_1") (pintype "passive"))
    )
    (net (code "61") (name "unconnected-(CC4-PadGDO0)") (class "Default")
      (node (ref "CC4") (pin "GDO0") (pinfunction "GDO0_GDO0") (pintype "bidirectional"))
    )
    (net (code "62") (name "unconnected-(CC_X3-Pad8)") (class "Default")
      (node (ref "CC_X3") (pin "8") (pinfunction "8_8") (pintype "passive"))
    )
    (net (code "63") (name "unconnected-(CTX-DBH-S-Pad7)") (class "Default")
      (node (ref "CTX-DB") (pin "7") (pinfunction "S_7") (pintype "passive"))
    )
    (net (code "64") (name "unconnected-(ESP8266-PadGPIO2)") (class "Default")
      (node (ref "ESP8266") (pin "GPIO2") (pinfunction "GPIO2_GPIO2") (pintype "bidirectional"))
    )
    (net (code "65") (name "unconnected-(ESP8266-PadGPIO12)") (class "Default")
      (node (ref "ESP8266") (pin "GPIO12") (pinfunction "GPIO12_GPIO12") (pintype "bidirectional"))
    )
    (net (code "66") (name "unconnected-(ESP8266-PadGPIO13)") (class "Default")
      (node (ref "ESP8266") (pin "GPIO13") (pinfunction "GPIO13_GPIO13") (pintype "bidirectional"))
    )
    (net (code "67") (name "unconnected-(ESP8266-PadGPIO14)") (class "Default")
      (node (ref "ESP8266") (pin "GPIO14") (pinfunction "GPIO14_GPIO14") (pintype "bidirectional"))
    )
    (net (code "68") (name "unconnected-(ESP8266-PadGPIO18)") (class "Default")
      (node (ref "ESP8266") (pin "GPIO18") (pinfunction "GPIO18_GPIO18") (pintype "bidirectional"))
    )
    (net (code "69") (name "unconnected-(ESP8266-PadNC)") (class "Default")
      (node (ref "ESP8266") (pin "NC") (pinfunction "NC_NC") (pintype "bidirectional"))
    )
    (net (code "70") (name "unconnected-(HMMOD-UART-C2D-Pad3)") (class "Default")
      (node (ref "HMMOD-UART") (pin "3") (pinfunction "C2D_3") (pintype "bidirectional"))
    )
    (net (code "71") (name "unconnected-(HMMOD-UART-\\~{RESET}-Pad4)") (class "Default")
      (node (ref "HMMOD-UART") (pin "4") (pinfunction "\\~{RESET}_4") (pintype "bidirectional"))
    )
    (net (code "72") (name "unconnected-(IC2-NC-Pad9)") (class "Default")
      (node (ref "IC2") (pin "9") (pinfunction "NC_9") (pintype "no_connect"))
    )
    (net (code "73") (name "unconnected-(U$1-23{slash}USB_DP-Pad12)") (class "Default")
      (node (ref "U$1") (pin "12") (pinfunction "23/USB_DP_12") (pintype "bidirectional"))
    )
    (net (code "74") (name "unconnected-(U$1-24{slash}USB_DM-Pad13)") (class "Default")
      (node (ref "U$1") (pin "13") (pinfunction "24/USB_DM_13") (pintype "bidirectional"))
    )
    (net (code "75") (name "unconnected-(U$1-BUT-Pad3)") (class "Default")
      (node (ref "U$1") (pin "3") (pinfunction "BUT_3") (pintype "bidirectional"))
    )
    (net (code "76") (name "unconnected-(U$1-VBAT-Pad38)") (class "Default")
      (node (ref "U$1") (pin "38") (pinfunction "VBAT_38") (pintype "bidirectional"))
    )
    (net (code "77") (name "unconnected-(U$1-VCC-Pad1)") (class "Default")
      (node (ref "U$1") (pin "1") (pinfunction "VCC_1") (pintype "bidirectional"))
    )
    (net (code "78") (name "unconnected-(U$2-GND1-PadGND4)") (class "Default")
      (node (ref "U$2") (pin "GND4") (pinfunction "GND1_GND4") (pintype "bidirectional"))
    )
    (net (code "79") (name "unconnected-(U$2-GND2-PadGND1)") (class "Default")
      (node (ref "U$2") (pin "GND1") (pinfunction "GND2_GND1") (pintype "bidirectional"))
    )
    (net (code "80") (name "unconnected-(U$2-GND3-PadGND2)") (class "Default")
      (node (ref "U$2") (pin "GND2") (pinfunction "GND3_GND2") (pintype "bidirectional"))
    )
    (net (code "81") (name "unconnected-(U$2-GND4-PadGND3)") (class "Default")
      (node (ref "U$2") (pin "GND3") (pinfunction "GND4_GND3") (pintype "bidirectional"))
    )
    (net (code "82") (name "unconnected-(U$2-PadA0)") (class "Default")
      (node (ref "U$2") (pin "A0") (pinfunction "A0_A0") (pintype "bidirectional"))
    )
    (net (code "83") (name "unconnected-(U$2-PadA1)") (class "Default")
      (node (ref "U$2") (pin "A1") (pinfunction "A1_A1") (pintype "bidirectional"))
    )
    (net (code "84") (name "unconnected-(U$2-PadA2)") (class "Default")
      (node (ref "U$2") (pin "A2") (pinfunction "A2_A2") (pintype "bidirectional"))
    )
    (net (code "85") (name "unconnected-(U$2-PadA3)") (class "Default")
      (node (ref "U$2") (pin "A3") (pinfunction "A3_A3") (pintype "bidirectional"))
    )
    (net (code "86") (name "unconnected-(U$2-PadA4)") (class "Default")
      (node (ref "U$2") (pin "A4") (pinfunction "A4_A4") (pintype "bidirectional"))
    )
    (net (code "87") (name "unconnected-(U$2-PadA5)") (class "Default")
      (node (ref "U$2") (pin "A5") (pinfunction "A5_A5") (pintype "bidirectional"))
    )
    (net (code "88") (name "unconnected-(U$2-PadA6)") (class "Default")
      (node (ref "U$2") (pin "A6") (pinfunction "A6_A6") (pintype "bidirectional"))
    )
    (net (code "89") (name "unconnected-(U$2-PadA7)") (class "Default")
      (node (ref "U$2") (pin "A7") (pinfunction "A7_A7") (pintype "bidirectional"))
    )
    (net (code "90") (name "unconnected-(U$2-PadD3)") (class "Default")
      (node (ref "U$2") (pin "D3") (pinfunction "D3_D3") (pintype "bidirectional"))
    )
    (net (code "91") (name "unconnected-(U$2-PadD4)") (class "Default")
      (node (ref "U$2") (pin "D4") (pinfunction "D4_D4") (pintype "bidirectional"))
    )
    (net (code "92") (name "unconnected-(U$2-PadD5)") (class "Default")
      (node (ref "U$2") (pin "D5") (pinfunction "D5_D5") (pintype "bidirectional"))
    )
    (net (code "93") (name "unconnected-(U$2-PadD6)") (class "Default")
      (node (ref "U$2") (pin "D6") (pinfunction "D6_D6") (pintype "bidirectional"))
    )
    (net (code "94") (name "unconnected-(U$2-PadD7)") (class "Default")
      (node (ref "U$2") (pin "D7") (pinfunction "D7_D7") (pintype "bidirectional"))
    )
    (net (code "95") (name "unconnected-(U$2-PadDTR)") (class "Default")
      (node (ref "U$2") (pin "DTR") (pinfunction "DTR_DTR") (pintype "bidirectional"))
    )
    (net (code "96") (name "unconnected-(U$2-PadRAW)") (class "Default")
      (node (ref "U$2") (pin "RAW") (pinfunction "RAW_RAW") (pintype "bidirectional"))
    )
    (net (code "97") (name "unconnected-(U$2-PadRST)") (class "Default")
      (node (ref "U$2") (pin "RST") (pinfunction "RST_RST") (pintype "bidirectional"))
    )
    (net (code "98") (name "unconnected-(U$2-PadRST1)") (class "Default")
      (node (ref "U$2") (pin "RST1") (pinfunction "RST1_RST1") (pintype "bidirectional"))
    )
    (net (code "99") (name "unconnected-(U$2-PadRX1-1)") (class "Default")
      (node (ref "U$2") (pin "RX1-1") (pinfunction "RX1-1_RX1-1") (pintype "bidirectional"))
    )
    (net (code "100") (name "unconnected-(U$2-PadTX0-1)") (class "Default")
      (node (ref "U$2") (pin "TX0-1") (pinfunction "TX0-1_TX0-1") (pintype "bidirectional"))
    )
    (net (code "101") (name "unconnected-(U$2-PadVCC1)") (class "Default")
      (node (ref "U$2") (pin "VCC1") (pinfunction "VCC1_VCC1") (pintype "bidirectional"))
    )
    (net (code "102") (name "unconnected-(U$3-PadGPIO2)") (class "Default")
      (node (ref "U$3") (pin "GPIO2") (pinfunction "GPIO2_GPIO2") (pintype "bidirectional"))
    )
    (net (code "103") (name "unconnected-(U$3-PadRST)") (class "Default")
      (node (ref "U$3") (pin "RST") (pinfunction "RST_RST") (pintype "bidirectional"))
    )
  )
)
